# elektrosluch.net
KiCad netlist of a schematic drawn in EAGLE
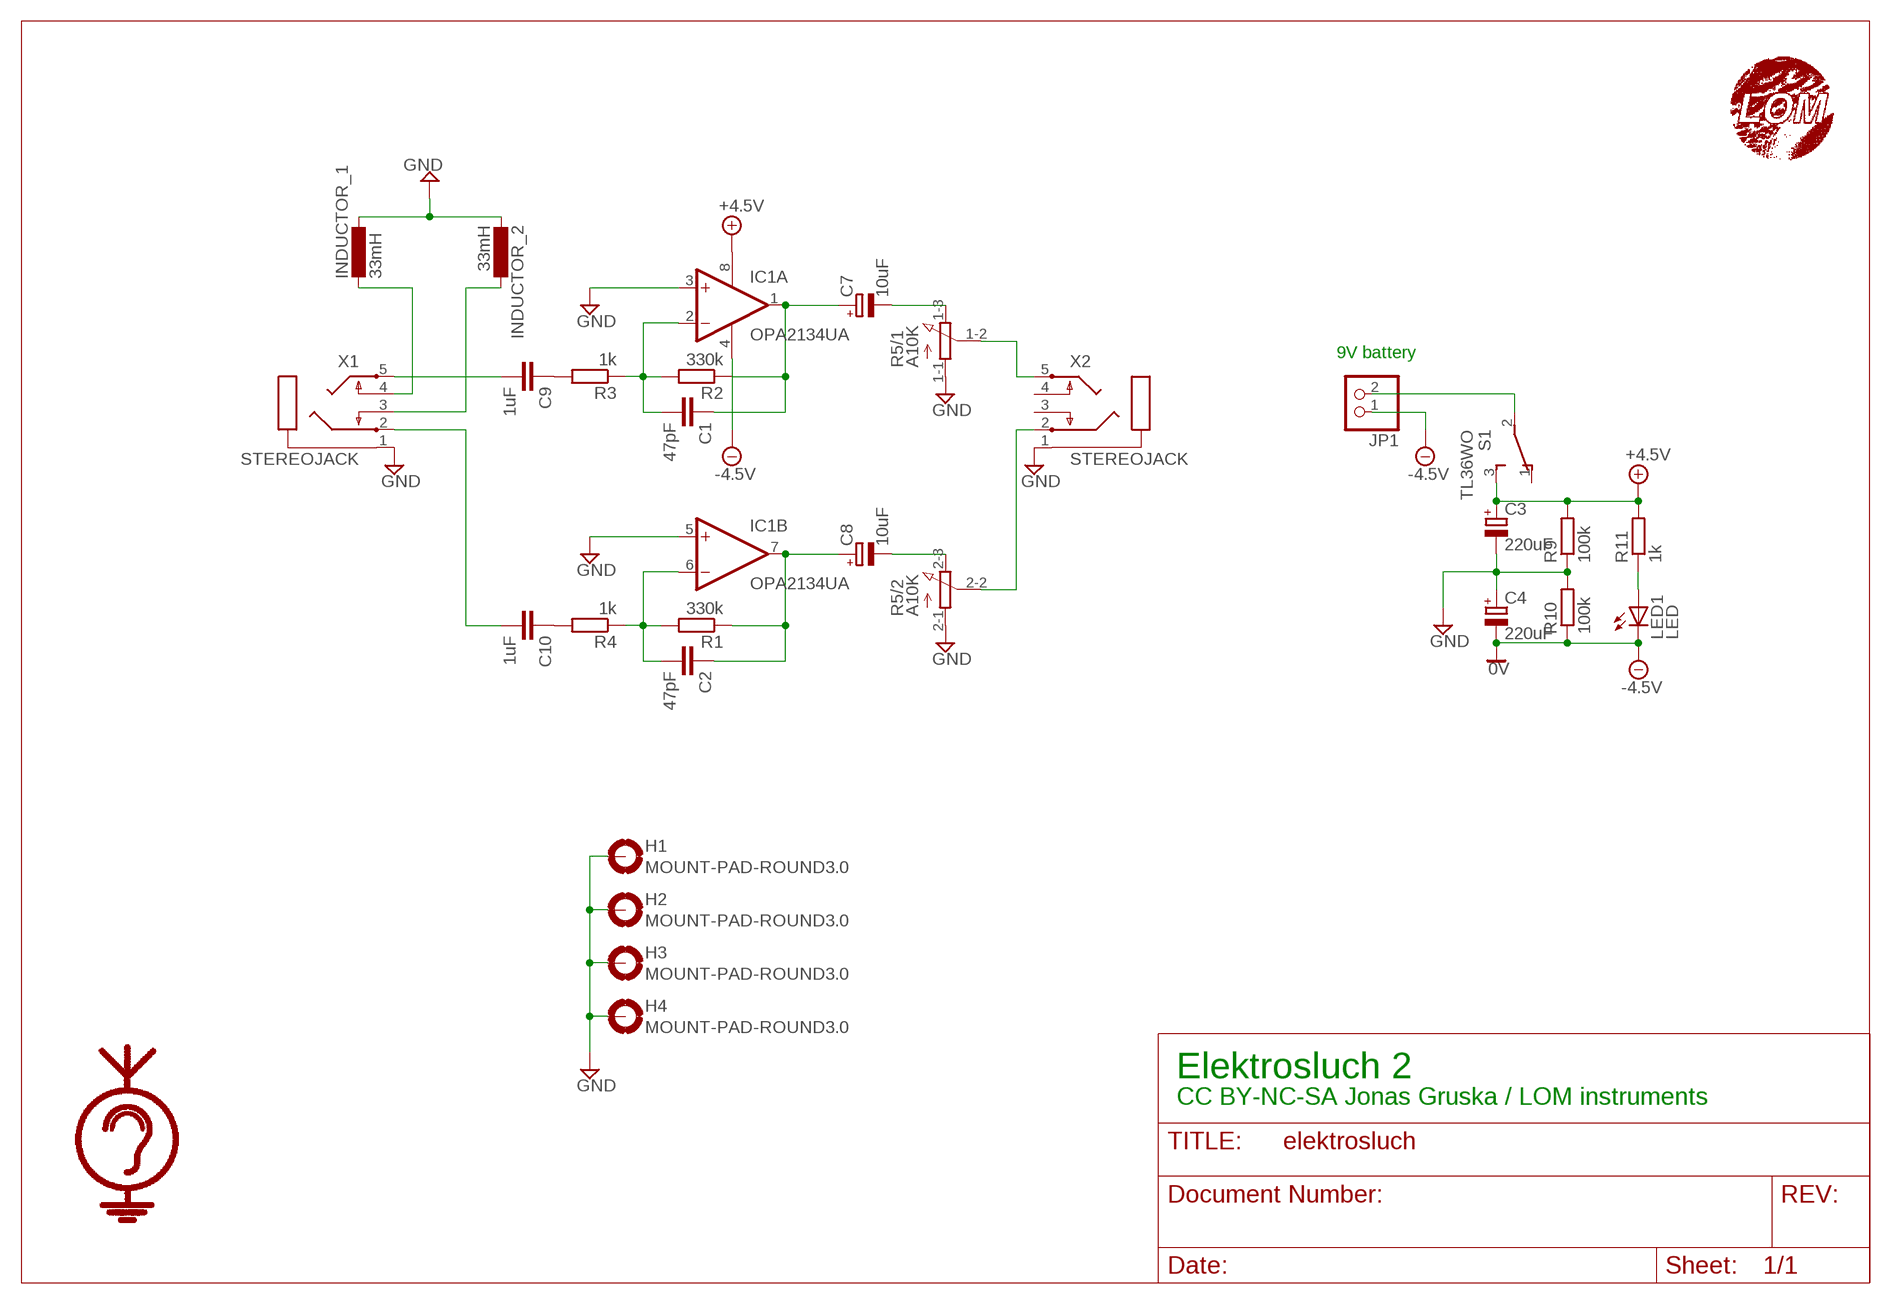
[diagram p0: schematic, sheet 1]

(export (version "E")
  (design (tool "Eeschema 10.0.6"))
  (components
    (comp (ref "C1")
      (value "47pF")
      (footprint "eagle-import:C1206")
      (libsource (lib "eagle-import") (part "C-EUC1206"))
    )
    (comp (ref "C2")
      (value "47pF")
      (footprint "eagle-import:C1206")
      (libsource (lib "eagle-import") (part "C-EUC1206"))
    )
    (comp (ref "C3")
      (value "220uF")
      (footprint "eagle-import:PANASONIC_D")
      (libsource (lib "eagle-import") (part "CPOL-EUD"))
    )
    (comp (ref "C4")
      (value "220uF")
      (footprint "eagle-import:PANASONIC_D")
      (libsource (lib "eagle-import") (part "CPOL-EUD"))
    )
    (comp (ref "C7")
      (value "10uF")
      (footprint "eagle-import:PANASONIC_B")
      (libsource (lib "eagle-import") (part "CPOL-EUB"))
    )
    (comp (ref "C8")
      (value "10uF")
      (footprint "eagle-import:PANASONIC_B")
      (libsource (lib "eagle-import") (part "CPOL-EUB"))
    )
    (comp (ref "C9")
      (value "1uF")
      (footprint "eagle-import:C1812")
      (libsource (lib "eagle-import") (part "C-EUC1812"))
    )
    (comp (ref "C10")
      (value "1uF")
      (footprint "eagle-import:C1812")
      (libsource (lib "eagle-import") (part "C-EUC1812"))
    )
    (comp (ref "H1")
      (value "MOUNT-PAD-ROUND3.0")
      (footprint "eagle-import:3,0-PAD")
      (libsource (lib "eagle-import") (part "MOUNT-PAD-ROUND3.0"))
    )
    (comp (ref "H2")
      (value "MOUNT-PAD-ROUND3.0")
      (footprint "eagle-import:3,0-PAD")
      (libsource (lib "eagle-import") (part "MOUNT-PAD-ROUND3.0"))
    )
    (comp (ref "H3")
      (value "MOUNT-PAD-ROUND3.0")
      (footprint "eagle-import:3,0-PAD")
      (libsource (lib "eagle-import") (part "MOUNT-PAD-ROUND3.0"))
    )
    (comp (ref "H4")
      (value "MOUNT-PAD-ROUND3.0")
      (footprint "eagle-import:3,0-PAD")
      (libsource (lib "eagle-import") (part "MOUNT-PAD-ROUND3.0"))
    )
    (comp (ref "IC1")
      (value "OPA2134UA")
      (footprint "eagle-import:SO08")
      (libsource (lib "eagle-import") (part "OPA2UA134"))
    )
    (comp (ref "INDUCTOR_1")
      (value "33mH")
      (footprint "eagle-import:COIL")
      (libsource (lib "eagle-import") (part "COIL"))
    )
    (comp (ref "INDUCTOR_2")
      (value "33mH")
      (footprint "eagle-import:COIL")
      (libsource (lib "eagle-import") (part "COIL"))
    )
    (comp (ref "JP1")
      (value "PINHD-1X2")
      (footprint "eagle-import:1X02")
      (libsource (lib "eagle-import") (part "PINHD-1X2"))
    )
    (comp (ref "LED1")
      (value "LED")
      (footprint "eagle-import:LED3MM")
      (libsource (lib "eagle-import") (part "LED"))
    )
    (comp (ref "R1")
      (value "330k")
      (footprint "eagle-import:M1206")
      (libsource (lib "eagle-import") (part "R-EU_M1206"))
    )
    (comp (ref "R2")
      (value "330k")
      (footprint "eagle-import:M1206")
      (libsource (lib "eagle-import") (part "R-EU_M1206"))
    )
    (comp (ref "R3")
      (value "1k")
      (footprint "eagle-import:M1206")
      (libsource (lib "eagle-import") (part "R-EU_M1206"))
    )
    (comp (ref "R4")
      (value "1k")
      (footprint "eagle-import:M1206")
      (libsource (lib "eagle-import") (part "R-EU_M1206"))
    )
    (comp (ref "R5")
      (value "A10K")
      (footprint "eagle-import:3RP_1610G")
      (libsource (lib "eagle-import") (part "3RP/1610G"))
    )
    (comp (ref "R9")
      (value "100k")
      (footprint "eagle-import:M1206")
      (libsource (lib "eagle-import") (part "R-EU_M1206"))
    )
    (comp (ref "R10")
      (value "100k")
      (footprint "eagle-import:M1206")
      (libsource (lib "eagle-import") (part "R-EU_M1206"))
    )
    (comp (ref "R11")
      (value "1k")
      (footprint "eagle-import:M1206")
      (libsource (lib "eagle-import") (part "R-EU_M1206"))
    )
    (comp (ref "S1")
      (value "TL36WO")
      (footprint "eagle-import:TL3XWO")
      (libsource (lib "eagle-import") (part "TL36WO"))
    )
    (comp (ref "U$3")
      (value "LOM")
      (footprint "eagle-import:LOMLOGO")
      (libsource (lib "eagle-import") (part "LOM"))
    )
    (comp (ref "U$5")
      (value "ELEKTROSLUCH")
      (footprint "eagle-import:ELEKTROSLUCH")
      (libsource (lib "eagle-import") (part "ELEKTROSLUCH"))
    )
    (comp (ref "X1")
      (value "STEREOJACK")
      (footprint "eagle-import:STX3100")
      (libsource (lib "eagle-import") (part "STEREOJACK"))
    )
    (comp (ref "X2")
      (value "STEREOJACK")
      (footprint "eagle-import:STX3100")
      (libsource (lib "eagle-import") (part "STEREOJACK"))
    )
  )
  (nets
    (net (code "1") (name "+4.5V") (class "Default")
      (node (ref "C3") (pin "+") (pinfunction "+_+") (pintype "passive"))
      (node (ref "IC1") (pin "8") (pinfunction "V+_8") (pintype "power_in"))
      (node (ref "R11") (pin "2") (pinfunction "2_2") (pintype "passive"))
      (node (ref "R9") (pin "2") (pinfunction "2_2") (pintype "passive"))
      (node (ref "S1") (pin "3") (pinfunction "S_3") (pintype "passive"))
    )
    (net (code "2") (name "-4.5V") (class "Default")
      (node (ref "C4") (pin "-") (pinfunction "-_-") (pintype "passive"))
      (node (ref "IC1") (pin "4") (pinfunction "V-_4") (pintype "power_in"))
      (node (ref "JP1") (pin "1") (pinfunction "1_1") (pintype "passive"))
      (node (ref "LED1") (pin "K") (pinfunction "C_K") (pintype "passive"))
      (node (ref "R10") (pin "1") (pinfunction "1_1") (pintype "passive"))
    )
    (net (code "3") (name "GND") (class "Default")
      (node (ref "C3") (pin "-") (pinfunction "-_-") (pintype "passive"))
      (node (ref "C4") (pin "+") (pinfunction "+_+") (pintype "passive"))
      (node (ref "H1") (pin "B3,0") (pinfunction "MOUNT_B3,0") (pintype "passive"))
      (node (ref "H2") (pin "B3,0") (pinfunction "MOUNT_B3,0") (pintype "passive"))
      (node (ref "H3") (pin "B3,0") (pinfunction "MOUNT_B3,0") (pintype "passive"))
      (node (ref "H4") (pin "B3,0") (pinfunction "MOUNT_B3,0") (pintype "passive"))
      (node (ref "IC1") (pin "3") (pinfunction "+IN_3") (pintype "input"))
      (node (ref "IC1") (pin "5") (pinfunction "+IN_5") (pintype "input"))
      (node (ref "INDUCTOR_1") (pin "P$1") (pinfunction "1_P$1") (pintype "passive"))
      (node (ref "INDUCTOR_2") (pin "P$2") (pinfunction "2_P$2") (pintype "passive"))
      (node (ref "R10") (pin "2") (pinfunction "2_2") (pintype "passive"))
      (node (ref "R5") (pin "1-1") (pinfunction "1_1-1") (pintype "passive"))
      (node (ref "R5") (pin "2-1") (pinfunction "1_2-1") (pintype "passive"))
      (node (ref "R9") (pin "1") (pinfunction "1_1") (pintype "passive"))
      (node (ref "X1") (pin "1") (pinfunction "1_1") (pintype "passive"))
      (node (ref "X2") (pin "1") (pinfunction "1_1") (pintype "passive"))
    )
    (net (code "4") (name "Net-(C9-Pad1)") (class "Default")
      (node (ref "C9") (pin "1") (pinfunction "1_1") (pintype "passive"))
      (node (ref "R3") (pin "2") (pinfunction "2_2") (pintype "passive"))
    )
    (net (code "5") (name "Net-(C9-Pad2)") (class "Default")
      (node (ref "C9") (pin "2") (pinfunction "2_2") (pintype "passive"))
      (node (ref "X1") (pin "5") (pinfunction "5_5") (pintype "passive"))
    )
    (net (code "6") (name "Net-(C10-Pad1)") (class "Default")
      (node (ref "C10") (pin "1") (pinfunction "1_1") (pintype "passive"))
      (node (ref "R4") (pin "2") (pinfunction "2_2") (pintype "passive"))
    )
    (net (code "7") (name "Net-(C10-Pad2)") (class "Default")
      (node (ref "C10") (pin "2") (pinfunction "2_2") (pintype "passive"))
      (node (ref "X1") (pin "2") (pinfunction "2_2") (pintype "passive"))
    )
    (net (code "8") (name "Net-(IC1A--IN)") (class "Default")
      (node (ref "C1") (pin "2") (pinfunction "2_2") (pintype "passive"))
      (node (ref "IC1") (pin "2") (pinfunction "-IN_2") (pintype "input"))
      (node (ref "R2") (pin "2") (pinfunction "2_2") (pintype "passive"))
      (node (ref "R3") (pin "1") (pinfunction "1_1") (pintype "passive"))
    )
    (net (code "9") (name "Net-(IC1A-OUT)") (class "Default")
      (node (ref "C1") (pin "1") (pinfunction "1_1") (pintype "passive"))
      (node (ref "C7") (pin "+") (pinfunction "+_+") (pintype "passive"))
      (node (ref "IC1") (pin "1") (pinfunction "OUT_1") (pintype "output"))
      (node (ref "R2") (pin "1") (pinfunction "1_1") (pintype "passive"))
    )
    (net (code "10") (name "Net-(IC1B--IN)") (class "Default")
      (node (ref "C2") (pin "2") (pinfunction "2_2") (pintype "passive"))
      (node (ref "IC1") (pin "6") (pinfunction "-IN_6") (pintype "input"))
      (node (ref "R1") (pin "2") (pinfunction "2_2") (pintype "passive"))
      (node (ref "R4") (pin "1") (pinfunction "1_1") (pintype "passive"))
    )
    (net (code "11") (name "Net-(IC1B-OUT)") (class "Default")
      (node (ref "C2") (pin "1") (pinfunction "1_1") (pintype "passive"))
      (node (ref "C8") (pin "+") (pinfunction "+_+") (pintype "passive"))
      (node (ref "IC1") (pin "7") (pinfunction "OUT_7") (pintype "output"))
      (node (ref "R1") (pin "1") (pinfunction "1_1") (pintype "passive"))
    )
    (net (code "12") (name "Net-(INDUCTOR_1-2)") (class "Default")
      (node (ref "INDUCTOR_1") (pin "P$2") (pinfunction "2_P$2") (pintype "passive"))
      (node (ref "X1") (pin "4") (pinfunction "4_4") (pintype "passive"))
    )
    (net (code "13") (name "Net-(INDUCTOR_2-1)") (class "Default")
      (node (ref "INDUCTOR_2") (pin "P$1") (pinfunction "1_P$1") (pintype "passive"))
      (node (ref "X1") (pin "3") (pinfunction "3_3") (pintype "passive"))
    )
    (net (code "14") (name "Net-(LED1-PadA)") (class "Default")
      (node (ref "LED1") (pin "A") (pinfunction "A_A") (pintype "passive"))
      (node (ref "R11") (pin "1") (pinfunction "1_1") (pintype "passive"))
    )
    (net (code "15") (name "Net-(R5A-2)") (class "Default")
      (node (ref "R5") (pin "1-2") (pinfunction "2_1-2") (pintype "passive"))
      (node (ref "X2") (pin "5") (pinfunction "5_5") (pintype "passive"))
    )
    (net (code "16") (name "Net-(R5A-3)") (class "Default")
      (node (ref "C7") (pin "-") (pinfunction "-_-") (pintype "passive"))
      (node (ref "R5") (pin "1-3") (pinfunction "3_1-3") (pintype "passive"))
    )
    (net (code "17") (name "Net-(R5B-2)") (class "Default")
      (node (ref "R5") (pin "2-2") (pinfunction "2_2-2") (pintype "passive"))
      (node (ref "X2") (pin "2") (pinfunction "2_2") (pintype "passive"))
    )
    (net (code "18") (name "Net-(R5B-3)") (class "Default")
      (node (ref "C8") (pin "-") (pinfunction "-_-") (pintype "passive"))
      (node (ref "R5") (pin "2-3") (pinfunction "3_2-3") (pintype "passive"))
    )
    (net (code "19") (name "Net-(S1-P)") (class "Default")
      (node (ref "JP1") (pin "2") (pinfunction "2_2") (pintype "passive"))
      (node (ref "S1") (pin "2") (pinfunction "P_2") (pintype "passive"))
    )
    (net (code "20") (name "unconnected-(S1-O-Pad1)") (class "Default")
      (node (ref "S1") (pin "1") (pinfunction "O_1") (pintype "passive"))
    )
    (net (code "21") (name "unconnected-(X2-Pad3)") (class "Default")
      (node (ref "X2") (pin "3") (pinfunction "3_3") (pintype "passive"))
    )
    (net (code "22") (name "unconnected-(X2-Pad4)") (class "Default")
      (node (ref "X2") (pin "4") (pinfunction "4_4") (pintype "passive"))
    )
  )
)
